# ART-Pi_F103_AP6212.net
KiCad netlist of a schematic drawn in Altium Designer
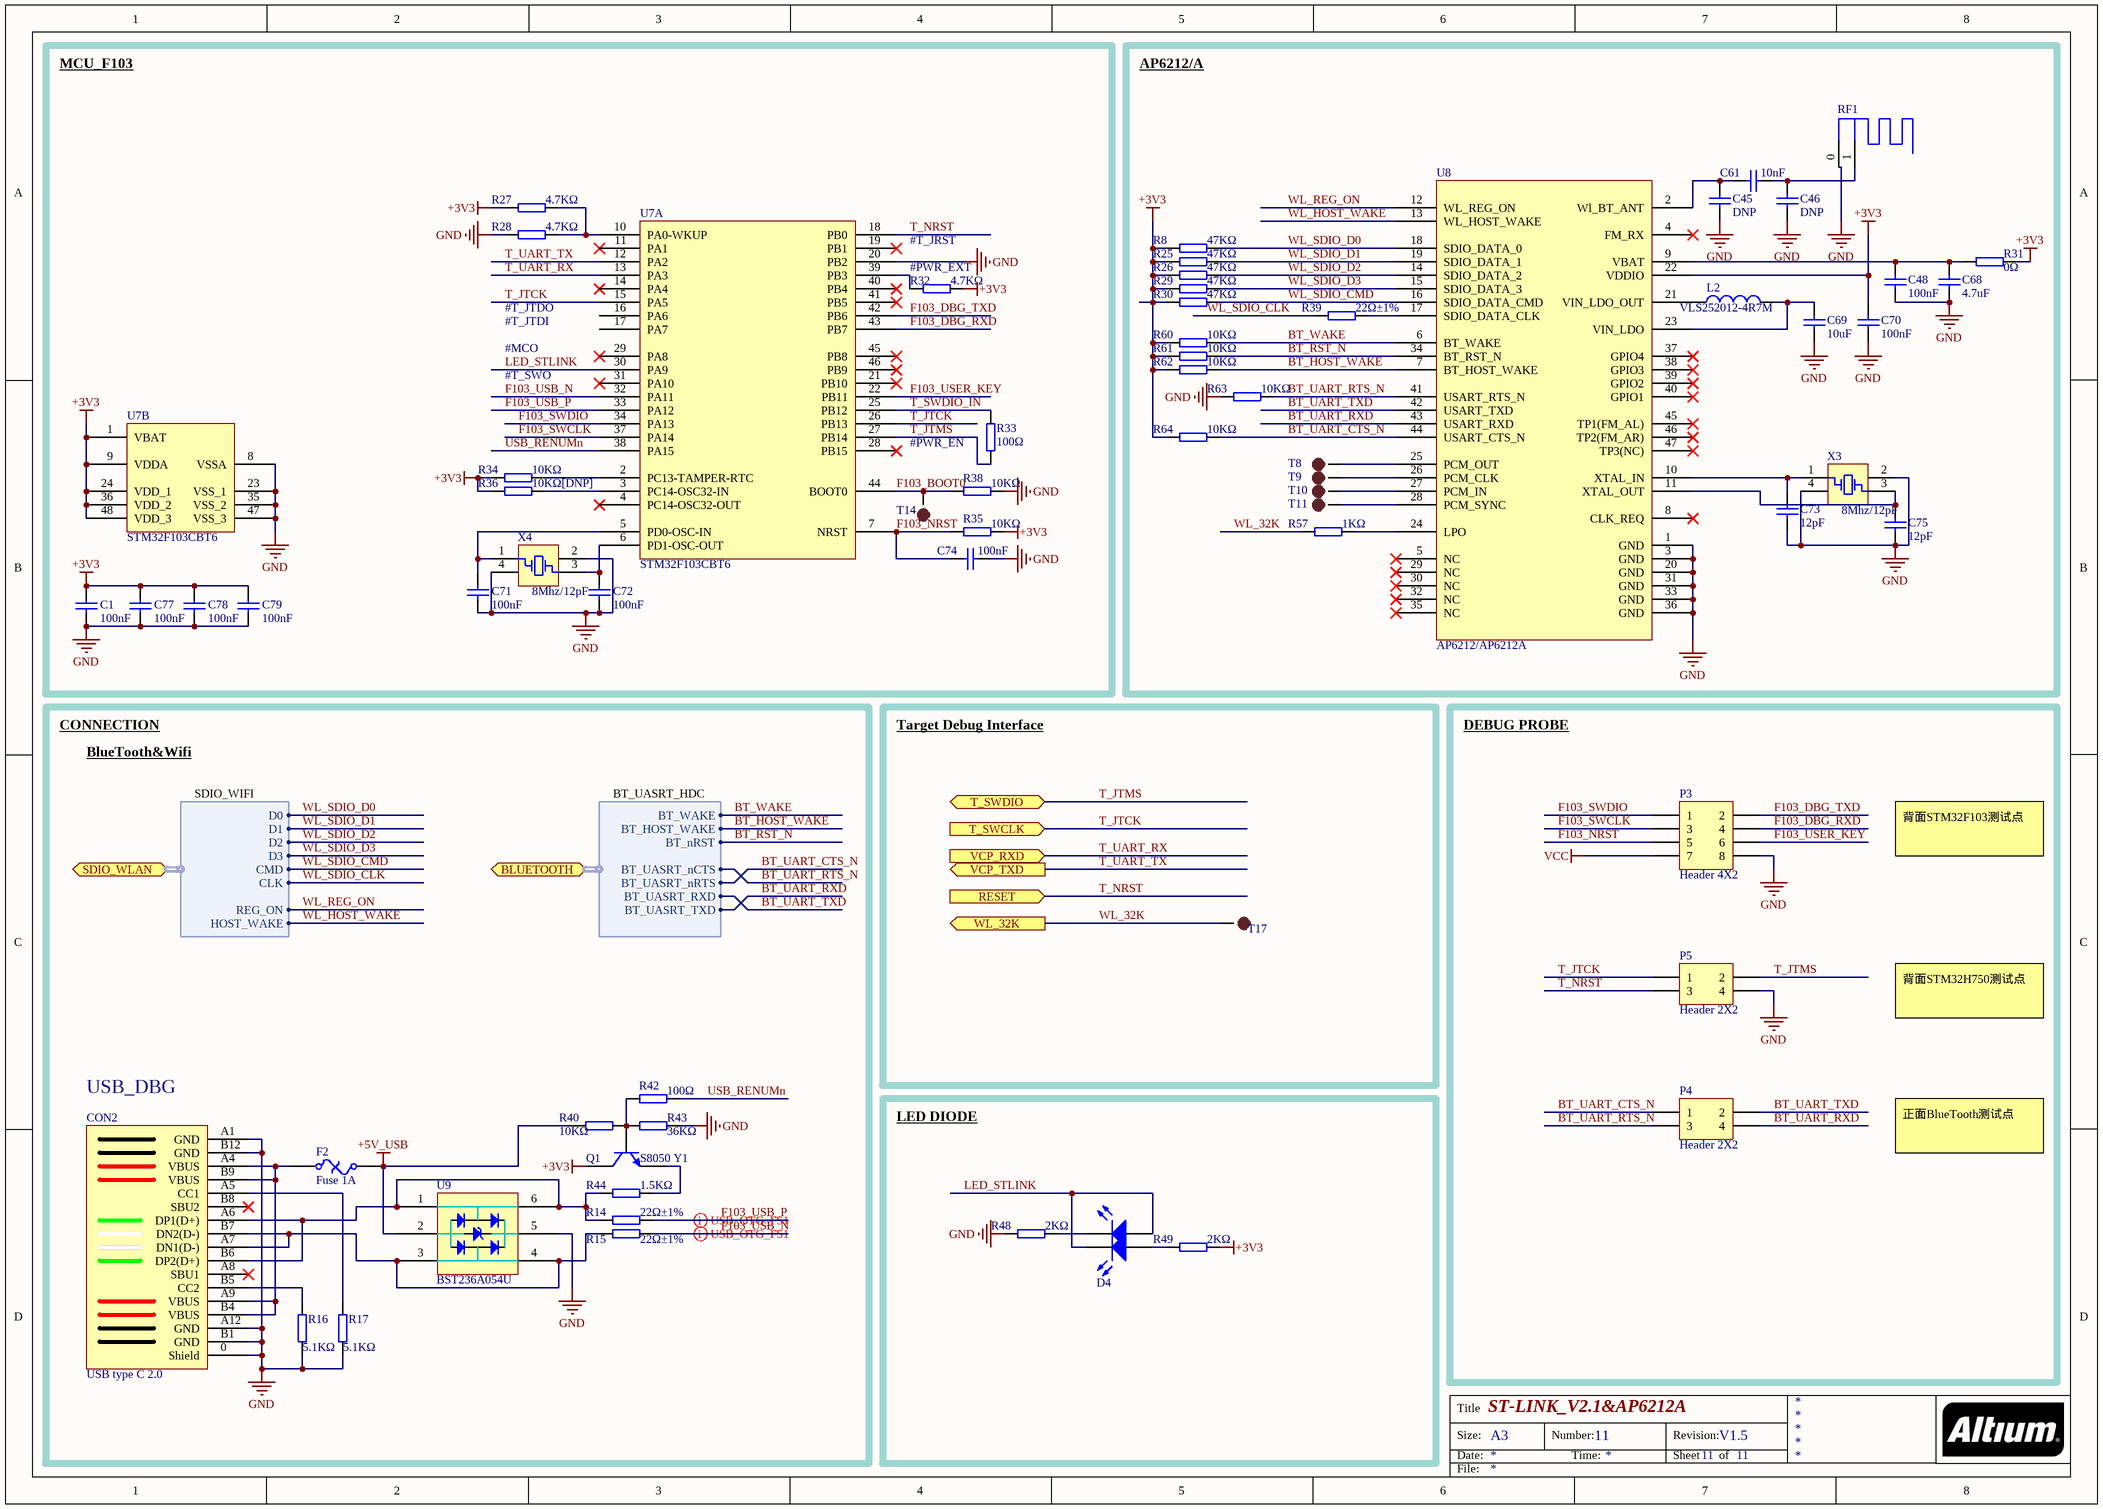
[diagram p0: ART-Pi_F103_AP6212.SchDoc]

(export (version "E")
  (design (tool "Eeschema 10.0.6"))
  (components
    (comp (ref "C1")
      (value "100nF")
      (footprint "0402_C")
      (description "Capacitor")
      (fields (field (name "PUBLISHER") "Altium Limited"))
      (libsource (lib "ART-Pi_STM32H750_COPY") (part "Cap"))
    )
    (comp (ref "C45")
      (value "DNP")
      (footprint "0402_C")
      (description "Capacitor")
      (fields (field (name "PUBLISHER") "Altium Limited"))
      (libsource (lib "ART-Pi_STM32H750_COPY") (part "Cap"))
    )
    (comp (ref "C46")
      (value "DNP")
      (footprint "0402_C")
      (description "Capacitor")
      (fields (field (name "PUBLISHER") "Altium Limited"))
      (libsource (lib "ART-Pi_STM32H750_COPY") (part "Cap"))
    )
    (comp (ref "C48")
      (value "100nF")
      (footprint "0402_C")
      (description "Capacitor")
      (fields (field (name "PUBLISHER") "Altium Limited"))
      (libsource (lib "ART-Pi_STM32H750_COPY") (part "Cap"))
    )
    (comp (ref "C61")
      (value "10nF")
      (footprint "0402_C")
      (description "Capacitor")
      (fields (field (name "PUBLISHER") "Altium Limited"))
      (libsource (lib "ART-Pi_STM32H750_COPY") (part "Cap"))
    )
    (comp (ref "C68")
      (value "4.7uF")
      (footprint "0402_C")
      (description "Capacitor")
      (fields (field (name "PUBLISHER") "Altium Limited"))
      (libsource (lib "ART-Pi_STM32H750_COPY") (part "Cap"))
    )
    (comp (ref "C69")
      (value "10uF")
      (footprint "0402_C")
      (description "Capacitor")
      (fields (field (name "PUBLISHER") "Altium Limited"))
      (libsource (lib "ART-Pi_STM32H750_COPY") (part "Cap"))
    )
    (comp (ref "C70")
      (value "100nF")
      (footprint "0402_C")
      (description "Capacitor")
      (fields (field (name "PUBLISHER") "Altium Limited"))
      (libsource (lib "ART-Pi_STM32H750_COPY") (part "Cap"))
    )
    (comp (ref "C71")
      (value "100nF")
      (footprint "0402_C")
      (description "Capacitor")
      (fields (field (name "PUBLISHER") "Altium Limited"))
      (libsource (lib "ART-Pi_STM32H750_COPY") (part "Cap"))
    )
    (comp (ref "C72")
      (value "100nF")
      (footprint "0402_C")
      (description "Capacitor")
      (fields (field (name "PUBLISHER") "Altium Limited"))
      (libsource (lib "ART-Pi_STM32H750_COPY") (part "Cap"))
    )
    (comp (ref "C73")
      (value "12pF")
      (footprint "0402_C")
      (description "Capacitor")
      (fields (field (name "PUBLISHER") "Altium Limited"))
      (libsource (lib "ART-Pi_STM32H750_COPY") (part "Cap"))
    )
    (comp (ref "C74")
      (value "100nF")
      (footprint "0402_C")
      (description "Capacitor")
      (fields (field (name "PUBLISHER") "Altium Limited"))
      (libsource (lib "ART-Pi_STM32H750_COPY") (part "Cap"))
    )
    (comp (ref "C75")
      (value "12pF")
      (footprint "0402_C")
      (description "Capacitor")
      (fields (field (name "PUBLISHER") "Altium Limited"))
      (libsource (lib "ART-Pi_STM32H750_COPY") (part "Cap"))
    )
    (comp (ref "C77")
      (value "100nF")
      (footprint "0402_C")
      (description "Capacitor")
      (fields (field (name "PUBLISHER") "Altium Limited"))
      (libsource (lib "ART-Pi_STM32H750_COPY") (part "Cap"))
    )
    (comp (ref "C78")
      (value "100nF")
      (footprint "0402_C")
      (description "Capacitor")
      (fields (field (name "PUBLISHER") "Altium Limited"))
      (libsource (lib "ART-Pi_STM32H750_COPY") (part "Cap"))
    )
    (comp (ref "C79")
      (value "100nF")
      (footprint "0402_C")
      (description "Capacitor")
      (fields (field (name "PUBLISHER") "Altium Limited"))
      (libsource (lib "ART-Pi_STM32H750_COPY") (part "Cap"))
    )
    (comp (ref "CON2")
      (value "USB type C 2.0")
      (footprint "USB_C")
      (libsource (lib "ART-Pi_STM32H750_COPY") (part "USB type C"))
    )
    (comp (ref "D4")
      (value "LED2")
      (footprint "LED2-0603")
      (description "Typical RED, GREEN, YELLOW, AMBER GaAs LED")
      (fields (field (name "PUBLISHER") "Altium Limited"))
      (libsource (lib "ART-Pi_STM32H750_COPY") (part "LED2"))
    )
    (comp (ref "F2")
      (value "Fuse 1A")
      (footprint "0805_R")
      (description "Thermal Fuse")
      (fields (field (name "PUBLISHER") "Altium Limited"))
      (libsource (lib "Miscellaneous Devices") (part "Fuse Thermal"))
    )
    (comp (ref "L2")
      (value "VLS252012-4R7M")
      (footprint "FNR252012S")
      (description "Inductor")
      (fields (field (name "PUBLISHER") "Altium Limited"))
      (libsource (lib "ART-Pi_STM32H750_COPY") (part "Inductor"))
    )
    (comp (ref "P3")
      (value "Header 4X2")
      (footprint "Test_Point_8")
      (description "Header, 4-Pin, Dual row")
      (fields (field (name "PUBLISHER") "Altium Limited"))
      (libsource (lib "Miscellaneous Connectors") (part "Header 4X2"))
    )
    (comp (ref "P4")
      (value "Header 2X2")
      (footprint "Test_Point_4")
      (description "Header, 2-Pin, Dual row")
      (fields (field (name "PUBLISHER") "Altium Limited"))
      (libsource (lib "Miscellaneous Connectors") (part "Header 2X2"))
    )
    (comp (ref "P5")
      (value "Header 2X2")
      (footprint "Test_Point_4")
      (description "Header, 2-Pin, Dual row")
      (fields (field (name "PUBLISHER") "Altium Limited"))
      (libsource (lib "Miscellaneous Connectors") (part "Header 2X2"))
    )
    (comp (ref "Q1")
      (value "S8050 Y1")
      (footprint "SOT23_P")
      (description "NPN Bipolar Transistor")
      (fields (field (name "PUBLISHER") "Altium Limited"))
      (libsource (lib "Miscellaneous Devices") (part "NPN"))
    )
    (comp (ref "R8")
      (value "47KΩ")
      (footprint "0402_R")
      (description "Resister")
      (libsource (lib "ART-Pi_STM32H750_COPY") (part "Res"))
    )
    (comp (ref "R14")
      (value "22Ω±1%")
      (footprint "0402_R")
      (description "Resister")
      (libsource (lib "ART-Pi_STM32H750_COPY") (part "Res"))
    )
    (comp (ref "R15")
      (value "22Ω±1%")
      (footprint "0402_R")
      (description "Resister")
      (libsource (lib "ART-Pi_STM32H750_COPY") (part "Res"))
    )
    (comp (ref "R16")
      (value "5.1KΩ")
      (footprint "0402_R")
      (description "Resister")
      (libsource (lib "ART-Pi_STM32H750_COPY") (part "Res"))
    )
    (comp (ref "R17")
      (value "5.1KΩ")
      (footprint "0402_R")
      (description "Resister")
      (libsource (lib "ART-Pi_STM32H750_COPY") (part "Res"))
    )
    (comp (ref "R25")
      (value "47KΩ")
      (footprint "0402_R")
      (description "Resister")
      (libsource (lib "ART-Pi_STM32H750_COPY") (part "Res"))
    )
    (comp (ref "R26")
      (value "47KΩ")
      (footprint "0402_R")
      (description "Resister")
      (libsource (lib "ART-Pi_STM32H750_COPY") (part "Res"))
    )
    (comp (ref "R27")
      (value "4.7KΩ")
      (footprint "0402_R")
      (description "Resister")
      (libsource (lib "ART-Pi_STM32H750_COPY") (part "Res"))
    )
    (comp (ref "R28")
      (value "4.7KΩ")
      (footprint "0402_R")
      (description "Resister")
      (libsource (lib "ART-Pi_STM32H750_COPY") (part "Res"))
    )
    (comp (ref "R29")
      (value "47KΩ")
      (footprint "0402_R")
      (description "Resister")
      (libsource (lib "ART-Pi_STM32H750_COPY") (part "Res"))
    )
    (comp (ref "R30")
      (value "47KΩ")
      (footprint "0402_R")
      (description "Resister")
      (libsource (lib "ART-Pi_STM32H750_COPY") (part "Res"))
    )
    (comp (ref "R31")
      (value "0Ω")
      (footprint "0402_R")
      (description "Resister")
      (libsource (lib "ART-Pi_STM32H750_COPY") (part "Res"))
    )
    (comp (ref "R32")
      (value "4.7KΩ")
      (footprint "0402_R")
      (description "Resister")
      (libsource (lib "ART-Pi_STM32H750_COPY") (part "Res"))
    )
    (comp (ref "R33")
      (value "100Ω")
      (footprint "0402_R")
      (description "Resister")
      (libsource (lib "ART-Pi_STM32H750_COPY") (part "Res"))
    )
    (comp (ref "R34")
      (value "10KΩ")
      (footprint "0402_R")
      (description "Resister")
      (libsource (lib "ART-Pi_STM32H750_COPY") (part "Res"))
    )
    (comp (ref "R35")
      (value "10KΩ")
      (footprint "0402_R")
      (description "Resister")
      (libsource (lib "ART-Pi_STM32H750_COPY") (part "Res"))
    )
    (comp (ref "R36")
      (value "10KΩ[DNP]")
      (footprint "0402_R")
      (description "Resister")
      (libsource (lib "ART-Pi_STM32H750_COPY") (part "Res"))
    )
    (comp (ref "R38")
      (value "10KΩ")
      (footprint "0402_R")
      (description "Resister")
      (libsource (lib "ART-Pi_STM32H750_COPY") (part "Res"))
    )
    (comp (ref "R39")
      (value "22Ω±1%")
      (footprint "0402_R")
      (description "Resister")
      (libsource (lib "ART-Pi_STM32H750_COPY") (part "Res"))
    )
    (comp (ref "R40")
      (value "10KΩ")
      (footprint "0402_R")
      (description "Resister")
      (libsource (lib "ART-Pi_STM32H750_COPY") (part "Res"))
    )
    (comp (ref "R42")
      (value "100Ω")
      (footprint "0402_R")
      (description "Resister")
      (libsource (lib "ART-Pi_STM32H750_COPY") (part "Res"))
    )
    (comp (ref "R43")
      (value "36KΩ")
      (footprint "0402_R")
      (description "Resister")
      (libsource (lib "ART-Pi_STM32H750_COPY") (part "Res"))
    )
    (comp (ref "R44")
      (value "1.5KΩ")
      (footprint "0402_R")
      (description "Resister")
      (libsource (lib "ART-Pi_STM32H750_COPY") (part "Res"))
    )
    (comp (ref "R48")
      (value "2KΩ")
      (footprint "0402_R")
      (description "Resister")
      (libsource (lib "ART-Pi_STM32H750_COPY") (part "Res"))
    )
    (comp (ref "R49")
      (value "2KΩ")
      (footprint "0402_R")
      (description "Resister")
      (libsource (lib "ART-Pi_STM32H750_COPY") (part "Res"))
    )
    (comp (ref "R57")
      (value "1KΩ")
      (footprint "0402_R")
      (description "Resister")
      (libsource (lib "ART-Pi_STM32H750_COPY") (part "Res"))
    )
    (comp (ref "R60")
      (value "10KΩ")
      (footprint "0402_R")
      (description "Resister")
      (libsource (lib "ART-Pi_STM32H750_COPY") (part "Res"))
    )
    (comp (ref "R61")
      (value "10KΩ")
      (footprint "0402_R")
      (description "Resister")
      (libsource (lib "ART-Pi_STM32H750_COPY") (part "Res"))
    )
    (comp (ref "R62")
      (value "10KΩ")
      (footprint "0402_R")
      (description "Resister")
      (libsource (lib "ART-Pi_STM32H750_COPY") (part "Res"))
    )
    (comp (ref "R63")
      (value "10KΩ")
      (footprint "0402_R")
      (description "Resister")
      (libsource (lib "ART-Pi_STM32H750_COPY") (part "Res"))
    )
    (comp (ref "R64")
      (value "10KΩ")
      (footprint "0402_R")
      (description "Resister")
      (libsource (lib "ART-Pi_STM32H750_COPY") (part "Res"))
    )
    (comp (ref "RF1")
      (value "ANT")
      (footprint "RF")
      (libsource (lib "ART-Pi_STM32H750_COPY") (part "PCB-ANT-2.4G-S"))
    )
    (comp (ref "T8")
      (value "TEST POINT")
      (footprint "Test_Point")
      (description "测试点")
      (libsource (lib "ART-Pi_STM32H750_COPY") (part "TEST-POINT"))
    )
    (comp (ref "T9")
      (value "TEST POINT")
      (footprint "Test_Point")
      (description "测试点")
      (libsource (lib "ART-Pi_STM32H750_COPY") (part "TEST-POINT"))
    )
    (comp (ref "T10")
      (value "TEST POINT")
      (footprint "Test_Point")
      (description "测试点")
      (libsource (lib "ART-Pi_STM32H750_COPY") (part "TEST-POINT"))
    )
    (comp (ref "T11")
      (value "TEST POINT")
      (footprint "Test_Point")
      (description "测试点")
      (libsource (lib "ART-Pi_STM32H750_COPY") (part "TEST-POINT"))
    )
    (comp (ref "T14")
      (value "TEST POINT")
      (footprint "Test_Point")
      (description "测试点")
      (libsource (lib "ART-Pi_STM32H750_COPY") (part "TEST-POINT"))
    )
    (comp (ref "T17")
      (value "TEST POINT")
      (footprint "Test_Point")
      (description "测试点")
      (libsource (lib "ART-Pi_STM32H750_COPY") (part "TEST-POINT"))
    )
    (comp (ref "U7")
      (value "STM32F103CBT6")
      (footprint "LQFP48_N")
      (libsource (lib "ART-Pi_STM32H750_COPY") (part "STM32F103CBT6"))
    )
    (comp (ref "U8")
      (value "AP6212/AP6212A")
      (footprint "AP6212A")
      (libsource (lib "ART-Pi_STM32H750_COPY") (part "AP6212/AP6212A"))
    )
    (comp (ref "U9")
      (value "BST236A054U")
      (footprint "SOT23_6")
      (libsource (lib "ART-Pi_STM32H750_COPY") (part "BST236A054U"))
    )
    (comp (ref "X3")
      (value "8Mhz/12pF")
      (footprint "SMD2520")
      (description "Crystal Oscillator")
      (fields (field (name "PUBLISHER") "Altium Limited"))
      (libsource (lib "ART-Pi_STM32H750_COPY") (part "XTAL_3225"))
    )
    (comp (ref "X4")
      (value "8Mhz/12pF")
      (footprint "XT-3225-4P")
      (description "Crystal Oscillator")
      (fields (field (name "PUBLISHER") "Altium Limited"))
      (libsource (lib "ART-Pi_STM32H750_COPY") (part "XTAL_3225"))
    )
  )
  (nets
    (net (code "2") (name "+3V3") (class "Default")
      (node (ref "C1") (pin "2") (pinfunction "2_2") (pintype "passive"))
      (node (ref "C70") (pin "1") (pinfunction "1_1") (pintype "passive"))
      (node (ref "C77") (pin "2") (pinfunction "2_2") (pintype "passive"))
      (node (ref "C78") (pin "2") (pinfunction "2_2") (pintype "passive"))
      (node (ref "C79") (pin "2") (pinfunction "2_2") (pintype "passive"))
      (node (ref "Q1") (pin "1") (pinfunction "C_1") (pintype "passive"))
      (node (ref "R25") (pin "1") (pinfunction "1_1") (pintype "passive"))
      (node (ref "R26") (pin "1") (pinfunction "1_1") (pintype "passive"))
      (node (ref "R27") (pin "2") (pinfunction "2_2") (pintype "passive"))
      (node (ref "R29") (pin "1") (pinfunction "1_1") (pintype "passive"))
      (node (ref "R30") (pin "1") (pinfunction "1_1") (pintype "passive"))
      (node (ref "R31") (pin "2") (pinfunction "2_2") (pintype "passive"))
      (node (ref "R32") (pin "1") (pinfunction "1_1") (pintype "passive"))
      (node (ref "R34") (pin "2") (pinfunction "2_2") (pintype "passive"))
      (node (ref "R35") (pin "2") (pinfunction "2_2") (pintype "passive"))
      (node (ref "R36") (pin "2") (pinfunction "2_2") (pintype "passive"))
      (node (ref "R49") (pin "2") (pinfunction "2_2") (pintype "passive"))
      (node (ref "R60") (pin "1") (pinfunction "1_1") (pintype "passive"))
      (node (ref "R61") (pin "1") (pinfunction "1_1") (pintype "passive"))
      (node (ref "R62") (pin "1") (pinfunction "1_1") (pintype "passive"))
      (node (ref "R64") (pin "1") (pinfunction "1_1") (pintype "passive"))
      (node (ref "R8") (pin "1") (pinfunction "1_1") (pintype "passive"))
      (node (ref "U7") (pin "1") (pinfunction "VBAT_1") (pintype "passive"))
      (node (ref "U7") (pin "24") (pinfunction "VDD_1_24") (pintype "passive"))
      (node (ref "U7") (pin "36") (pinfunction "VDD_2_36") (pintype "passive"))
      (node (ref "U7") (pin "48") (pinfunction "VDD_3_48") (pintype "passive"))
      (node (ref "U7") (pin "9") (pinfunction "VDDA_9") (pintype "passive"))
      (node (ref "U8") (pin "22") (pinfunction "VDDIO_22") (pintype "passive"))
    )
    (net (code "3") (name "+5V_USB") (class "Default")
      (node (ref "F2") (pin "2") (pinfunction "2_2") (pintype "passive"))
      (node (ref "R40") (pin "1") (pinfunction "1_1") (pintype "passive"))
      (node (ref "U9") (pin "2") (pinfunction "2_2") (pintype "passive"))
    )
    (net (code "4") (name "/BT_HOST_WAKE") (class "Default")
      (node (ref "R62") (pin "2") (pinfunction "2_2") (pintype "passive"))
      (node (ref "U8") (pin "7") (pinfunction "BT_HOST_WAKE_7") (pintype "passive"))
    )
    (net (code "5") (name "/BT_RST_N") (class "Default")
      (node (ref "R61") (pin "2") (pinfunction "2_2") (pintype "passive"))
      (node (ref "U8") (pin "34") (pinfunction "BT_RST_N_34") (pintype "passive"))
    )
    (net (code "6") (name "/BT_UART_CTS_N") (class "Default")
      (node (ref "P4") (pin "1") (pinfunction "1_1") (pintype "passive"))
      (node (ref "R64") (pin "2") (pinfunction "2_2") (pintype "passive"))
      (node (ref "U8") (pin "44") (pinfunction "USART_CTS_N_44") (pintype "passive"))
    )
    (net (code "7") (name "/BT_UART_RTS_N") (class "Default")
      (node (ref "P4") (pin "3") (pinfunction "3_3") (pintype "passive"))
      (node (ref "R63") (pin "2") (pinfunction "2_2") (pintype "passive"))
      (node (ref "U8") (pin "41") (pinfunction "USART_RTS_N_41") (pintype "passive"))
    )
    (net (code "8") (name "/BT_UART_RXD") (class "Default")
      (node (ref "P4") (pin "4") (pinfunction "4_4") (pintype "passive"))
      (node (ref "U8") (pin "43") (pinfunction "USART_RXD_43") (pintype "passive"))
    )
    (net (code "9") (name "/BT_UART_TXD") (class "Default")
      (node (ref "P4") (pin "2") (pinfunction "2_2") (pintype "passive"))
      (node (ref "U8") (pin "42") (pinfunction "USART_TXD_42") (pintype "passive"))
    )
    (net (code "10") (name "/BT_WAKE") (class "Default")
      (node (ref "R60") (pin "2") (pinfunction "2_2") (pintype "passive"))
      (node (ref "U8") (pin "6") (pinfunction "BT_WAKE_6") (pintype "passive"))
    )
    (net (code "11") (name "/F103_BOOT0") (class "Default")
      (node (ref "R38") (pin "1") (pinfunction "1_1") (pintype "passive"))
      (node (ref "T14") (pin "1") (pinfunction "1_1") (pintype "passive"))
      (node (ref "U7") (pin "44") (pinfunction "BOOT0_44") (pintype "passive"))
    )
    (net (code "12") (name "/F103_DBG_RXD") (class "Default")
      (node (ref "P3") (pin "4") (pinfunction "4_4") (pintype "passive"))
      (node (ref "U7") (pin "43") (pinfunction "PB7_43") (pintype "passive"))
    )
    (net (code "13") (name "/F103_DBG_TXD") (class "Default")
      (node (ref "P3") (pin "2") (pinfunction "2_2") (pintype "passive"))
      (node (ref "U7") (pin "42") (pinfunction "PB6_42") (pintype "passive"))
    )
    (net (code "14") (name "/F103_NRST") (class "Default")
      (node (ref "C74") (pin "2") (pinfunction "2_2") (pintype "passive"))
      (node (ref "P3") (pin "5") (pinfunction "5_5") (pintype "passive"))
      (node (ref "R35") (pin "1") (pinfunction "1_1") (pintype "passive"))
      (node (ref "U7") (pin "7") (pinfunction "NRST_7") (pintype "passive"))
    )
    (net (code "15") (name "/F103_SWCLK") (class "Default")
      (node (ref "P3") (pin "3") (pinfunction "3_3") (pintype "passive"))
      (node (ref "U7") (pin "37") (pinfunction "PA14_37") (pintype "passive"))
    )
    (net (code "16") (name "/F103_SWDIO") (class "Default")
      (node (ref "P3") (pin "1") (pinfunction "1_1") (pintype "passive"))
      (node (ref "U7") (pin "34") (pinfunction "PA13_34") (pintype "passive"))
    )
    (net (code "17") (name "/F103_USB_N") (class "Default")
      (node (ref "R15") (pin "2") (pinfunction "2_2") (pintype "passive"))
      (node (ref "U7") (pin "32") (pinfunction "PA11_32") (pintype "passive"))
    )
    (net (code "18") (name "/F103_USB_P") (class "Default")
      (node (ref "R14") (pin "2") (pinfunction "2_2") (pintype "passive"))
      (node (ref "U7") (pin "33") (pinfunction "PA12_33") (pintype "passive"))
    )
    (net (code "19") (name "/F103_USER_KEY") (class "Default")
      (node (ref "P3") (pin "6") (pinfunction "6_6") (pintype "passive"))
      (node (ref "U7") (pin "22") (pinfunction "PB11_22") (pintype "passive"))
    )
    (net (code "20") (name "/LED_STLINK") (class "Default")
      (node (ref "D4") (pin "2") (pinfunction "2_2") (pintype "passive"))
      (node (ref "D4") (pin "4") (pinfunction "4_4") (pintype "passive"))
      (node (ref "U7") (pin "30") (pinfunction "PA9_30") (pintype "passive"))
    )
    (net (code "21") (name "/T_JTCK") (class "Default")
      (node (ref "P5") (pin "1") (pinfunction "1_1") (pintype "passive"))
      (node (ref "U7") (pin "15") (pinfunction "PA5_15") (pintype "passive"))
      (node (ref "U7") (pin "26") (pinfunction "PB13_26") (pintype "passive"))
    )
    (net (code "22") (name "/T_JTMS") (class "Default")
      (node (ref "P5") (pin "2") (pinfunction "2_2") (pintype "passive"))
      (node (ref "R33") (pin "2") (pinfunction "2_2") (pintype "passive"))
      (node (ref "U7") (pin "27") (pinfunction "PB14_27") (pintype "passive"))
    )
    (net (code "23") (name "/T_NRST") (class "Default")
      (node (ref "P5") (pin "3") (pinfunction "3_3") (pintype "passive"))
      (node (ref "U7") (pin "18") (pinfunction "PB0_18") (pintype "passive"))
    )
    (net (code "24") (name "/T_SWDIO_IN") (class "Default")
      (node (ref "R33") (pin "1") (pinfunction "1_1") (pintype "passive"))
      (node (ref "U7") (pin "25") (pinfunction "PB12_25") (pintype "passive"))
    )
    (net (code "25") (name "/T_UART_RX") (class "Default")
      (node (ref "U7") (pin "13") (pinfunction "PA3_13") (pintype "passive"))
    )
    (net (code "26") (name "/T_UART_TX") (class "Default")
      (node (ref "U7") (pin "12") (pinfunction "PA2_12") (pintype "passive"))
    )
    (net (code "27") (name "/USB_RENUMn") (class "Default")
      (node (ref "R42") (pin "2") (pinfunction "2_2") (pintype "passive"))
      (node (ref "U7") (pin "38") (pinfunction "PA15_38") (pintype "passive"))
    )
    (net (code "28") (name "/WL_32K") (class "Default")
      (node (ref "R57") (pin "1") (pinfunction "1_1") (pintype "passive"))
      (node (ref "T17") (pin "1") (pinfunction "1_1") (pintype "passive"))
    )
    (net (code "29") (name "/WL_HOST_WAKE") (class "Default")
      (node (ref "U8") (pin "13") (pinfunction "WL_HOST_WAKE_13") (pintype "passive"))
    )
    (net (code "30") (name "/WL_REG_ON") (class "Default")
      (node (ref "U8") (pin "12") (pinfunction "WL_REG_ON_12") (pintype "passive"))
    )
    (net (code "31") (name "/WL_SDIO_CLK") (class "Default")
      (node (ref "R39") (pin "1") (pinfunction "1_1") (pintype "passive"))
    )
    (net (code "32") (name "/WL_SDIO_CMD") (class "Default")
      (node (ref "R30") (pin "2") (pinfunction "2_2") (pintype "passive"))
      (node (ref "U8") (pin "16") (pinfunction "SDIO_DATA_CMD_16") (pintype "passive"))
    )
    (net (code "33") (name "/WL_SDIO_D0") (class "Default")
      (node (ref "R8") (pin "2") (pinfunction "2_2") (pintype "passive"))
      (node (ref "U8") (pin "18") (pinfunction "SDIO_DATA_0_18") (pintype "passive"))
    )
    (net (code "34") (name "/WL_SDIO_D1") (class "Default")
      (node (ref "R25") (pin "2") (pinfunction "2_2") (pintype "passive"))
      (node (ref "U8") (pin "19") (pinfunction "SDIO_DATA_1_19") (pintype "passive"))
    )
    (net (code "35") (name "/WL_SDIO_D2") (class "Default")
      (node (ref "R26") (pin "2") (pinfunction "2_2") (pintype "passive"))
      (node (ref "U8") (pin "14") (pinfunction "SDIO_DATA_2_14") (pintype "passive"))
    )
    (net (code "36") (name "/WL_SDIO_D3") (class "Default")
      (node (ref "R29") (pin "2") (pinfunction "2_2") (pintype "passive"))
      (node (ref "U8") (pin "15") (pinfunction "SDIO_DATA_3_15") (pintype "passive"))
    )
    (net (code "38") (name "GND") (class "Default")
      (node (ref "C1") (pin "1") (pinfunction "1_1") (pintype "passive"))
      (node (ref "C45") (pin "2") (pinfunction "2_2") (pintype "passive"))
      (node (ref "C46") (pin "2") (pinfunction "2_2") (pintype "passive"))
      (node (ref "C48") (pin "2") (pinfunction "2_2") (pintype "passive"))
      (node (ref "C68") (pin "2") (pinfunction "2_2") (pintype "passive"))
      (node (ref "C69") (pin "2") (pinfunction "2_2") (pintype "passive"))
      (node (ref "C70") (pin "2") (pinfunction "2_2") (pintype "passive"))
      (node (ref "C71") (pin "1") (pinfunction "1_1") (pintype "passive"))
      (node (ref "C72") (pin "1") (pinfunction "1_1") (pintype "passive"))
      (node (ref "C73") (pin "2") (pinfunction "2_2") (pintype "passive"))
      (node (ref "C74") (pin "1") (pinfunction "1_1") (pintype "passive"))
      (node (ref "C75") (pin "2") (pinfunction "2_2") (pintype "passive"))
      (node (ref "C77") (pin "1") (pinfunction "1_1") (pintype "passive"))
      (node (ref "C78") (pin "1") (pinfunction "1_1") (pintype "passive"))
      (node (ref "C79") (pin "1") (pinfunction "1_1") (pintype "passive"))
      (node (ref "CON2") (pin "0") (pinfunction "Shield_0") (pintype "passive"))
      (node (ref "CON2") (pin "A1") (pinfunction "GND_A1") (pintype "passive"))
      (node (ref "CON2") (pin "A12") (pinfunction "GND_A12") (pintype "passive"))
      (node (ref "CON2") (pin "B1") (pinfunction "GND_B1") (pintype "passive"))
      (node (ref "CON2") (pin "B12") (pinfunction "GND_B12") (pintype "passive"))
      (node (ref "P3") (pin "8") (pinfunction "8_8") (pintype "passive"))
      (node (ref "P5") (pin "4") (pinfunction "4_4") (pintype "passive"))
      (node (ref "R16") (pin "2") (pinfunction "2_2") (pintype "passive"))
      (node (ref "R17") (pin "2") (pinfunction "2_2") (pintype "passive"))
      (node (ref "R28") (pin "2") (pinfunction "2_2") (pintype "passive"))
      (node (ref "R38") (pin "2") (pinfunction "2_2") (pintype "passive"))
      (node (ref "R43") (pin "2") (pinfunction "2_2") (pintype "passive"))
      (node (ref "R48") (pin "1") (pinfunction "1_1") (pintype "passive"))
      (node (ref "R63") (pin "1") (pinfunction "1_1") (pintype "passive"))
      (node (ref "RF1") (pin "0") (pinfunction "0_0") (pintype "passive"))
      (node (ref "U7") (pin "20") (pinfunction "PB2_20") (pintype "passive"))
      (node (ref "U7") (pin "23") (pinfunction "VSS_1_23") (pintype "passive"))
      (node (ref "U7") (pin "35") (pinfunction "VSS_2_35") (pintype "passive"))
      (node (ref "U7") (pin "47") (pinfunction "VSS_3_47") (pintype "passive"))
      (node (ref "U7") (pin "8") (pinfunction "VSSA_8") (pintype "passive"))
      (node (ref "U8") (pin "1") (pinfunction "GND_1") (pintype "passive"))
      (node (ref "U8") (pin "20") (pinfunction "GND_20") (pintype "passive"))
      (node (ref "U8") (pin "3") (pinfunction "GND_3") (pintype "passive"))
      (node (ref "U8") (pin "31") (pinfunction "GND_31") (pintype "passive"))
      (node (ref "U8") (pin "33") (pinfunction "GND_33") (pintype "passive"))
      (node (ref "U8") (pin "36") (pinfunction "GND_36") (pintype "passive"))
      (node (ref "U9") (pin "5") (pinfunction "5_5") (pintype "passive"))
      (node (ref "X3") (pin "2") (pinfunction "OSC2_2") (pintype "passive"))
      (node (ref "X3") (pin "4") (pinfunction "4_4") (pintype "passive"))
      (node (ref "X4") (pin "2") (pinfunction "OSC2_2") (pintype "passive"))
      (node (ref "X4") (pin "4") (pinfunction "4_4") (pintype "passive"))
    )
    (net (code "39") (name "Net-(C46-Pad1)") (class "Default")
      (node (ref "C46") (pin "1") (pinfunction "1_1") (pintype "passive"))
      (node (ref "C61") (pin "1") (pinfunction "1_1") (pintype "passive"))
      (node (ref "RF1") (pin "1") (pinfunction "1_1") (pintype "passive"))
    )
    (net (code "40") (name "Net-(CON2-CC1)") (class "Default")
      (node (ref "CON2") (pin "A5") (pinfunction "CC1_A5") (pintype "passive"))
      (node (ref "R17") (pin "1") (pinfunction "1_1") (pintype "passive"))
    )
    (net (code "41") (name "Net-(CON2-CC2)") (class "Default")
      (node (ref "CON2") (pin "B5") (pinfunction "CC2_B5") (pintype "passive"))
      (node (ref "R16") (pin "1") (pinfunction "1_1") (pintype "passive"))
    )
    (net (code "42") (name "Net-(CON2-DN1(D-))") (class "Default")
      (node (ref "CON2") (pin "A7") (pinfunction "DN1(D-)_A7") (pintype "passive"))
      (node (ref "CON2") (pin "B7") (pinfunction "DN2(D-)_B7") (pintype "passive"))
      (node (ref "R15") (pin "1") (pinfunction "1_1") (pintype "passive"))
      (node (ref "U9") (pin "3") (pinfunction "3_3") (pintype "passive"))
      (node (ref "U9") (pin "4") (pinfunction "4_4") (pintype "passive"))
    )
    (net (code "43") (name "Net-(CON2-DP1(D+))") (class "Default")
      (node (ref "CON2") (pin "A6") (pinfunction "DP1(D+)_A6") (pintype "passive"))
      (node (ref "CON2") (pin "B6") (pinfunction "DP2(D+)_B6") (pintype "passive"))
      (node (ref "R14") (pin "1") (pinfunction "1_1") (pintype "passive"))
      (node (ref "R44") (pin "1") (pinfunction "1_1") (pintype "passive"))
      (node (ref "U9") (pin "1") (pinfunction "1_1") (pintype "passive"))
      (node (ref "U9") (pin "6") (pinfunction "6_6") (pintype "passive"))
    )
    (net (code "44") (name "Net-(CON2-VBUS-PadA4)") (class "Default")
      (node (ref "CON2") (pin "A4") (pinfunction "VBUS_A4") (pintype "passive"))
      (node (ref "CON2") (pin "A9") (pinfunction "VBUS_A9") (pintype "passive"))
      (node (ref "CON2") (pin "B4") (pinfunction "VBUS_B4") (pintype "passive"))
      (node (ref "CON2") (pin "B9") (pinfunction "VBUS_B9") (pintype "passive"))
      (node (ref "F2") (pin "1") (pinfunction "1_1") (pintype "passive"))
    )
    (net (code "45") (name "Net-(D4-Pad1)") (class "Default")
      (node (ref "D4") (pin "1") (pinfunction "1_1") (pintype "passive"))
      (node (ref "R49") (pin "1") (pinfunction "1_1") (pintype "passive"))
    )
    (net (code "46") (name "Net-(D4-Pad3)") (class "Default")
      (node (ref "D4") (pin "3") (pinfunction "3_3") (pintype "passive"))
      (node (ref "R48") (pin "2") (pinfunction "2_2") (pintype "passive"))
    )
    (net (code "47") (name "Net-(Q1-B)") (class "Default")
      (node (ref "Q1") (pin "3") (pinfunction "B_3") (pintype "passive"))
      (node (ref "R40") (pin "2") (pinfunction "2_2") (pintype "passive"))
      (node (ref "R42") (pin "1") (pinfunction "1_1") (pintype "passive"))
      (node (ref "R43") (pin "1") (pinfunction "1_1") (pintype "passive"))
    )
    (net (code "48") (name "Net-(Q1-E)") (class "Default")
      (node (ref "Q1") (pin "2") (pinfunction "E_2") (pintype "passive"))
      (node (ref "R44") (pin "2") (pinfunction "2_2") (pintype "passive"))
    )
    (net (code "49") (name "Net-(U7A-PA0-WKUP)") (class "Default")
      (node (ref "R27") (pin "1") (pinfunction "1_1") (pintype "passive"))
      (node (ref "R28") (pin "1") (pinfunction "1_1") (pintype "passive"))
      (node (ref "U7") (pin "10") (pinfunction "PA0-WKUP_10") (pintype "passive"))
    )
    (net (code "50") (name "Net-(U7A-PB3)") (class "Default")
      (node (ref "R32") (pin "2") (pinfunction "2_2") (pintype "passive"))
      (node (ref "U7") (pin "39") (pinfunction "PB3_39") (pintype "passive"))
    )
    (net (code "51") (name "Net-(U7A-PC13-TAMPER-RTC)") (class "Default")
      (node (ref "R34") (pin "1") (pinfunction "1_1") (pintype "passive"))
      (node (ref "U7") (pin "2") (pinfunction "PC13-TAMPER-RTC_2") (pintype "passive"))
    )
    (net (code "52") (name "Net-(U7A-PC14-OSC32-IN)") (class "Default")
      (node (ref "R36") (pin "1") (pinfunction "1_1") (pintype "passive"))
      (node (ref "U7") (pin "3") (pinfunction "PC14-OSC32-IN_3") (pintype "passive"))
    )
    (net (code "53") (name "Net-(U7A-PD-OSC-IN)") (class "Default")
      (node (ref "C71") (pin "2") (pinfunction "2_2") (pintype "passive"))
      (node (ref "U7") (pin "5") (pinfunction "PD-OSC-IN_5") (pintype "passive"))
      (node (ref "X4") (pin "1") (pinfunction "OSC1_1") (pintype "passive"))
    )
    (net (code "54") (name "Net-(U7A-PD1-OSC-OUT)") (class "Default")
      (node (ref "C72") (pin "2") (pinfunction "2_2") (pintype "passive"))
      (node (ref "U7") (pin "6") (pinfunction "PD1-OSC-OUT_6") (pintype "passive"))
      (node (ref "X4") (pin "3") (pinfunction "3_3") (pintype "passive"))
    )
    (net (code "55") (name "Net-(U8-LPO)") (class "Default")
      (node (ref "R57") (pin "2") (pinfunction "2_2") (pintype "passive"))
      (node (ref "U8") (pin "24") (pinfunction "LPO_24") (pintype "passive"))
    )
    (net (code "56") (name "Net-(U8-PCM_CLK)") (class "Default")
      (node (ref "T9") (pin "1") (pinfunction "1_1") (pintype "passive"))
      (node (ref "U8") (pin "26") (pinfunction "PCM_CLK_26") (pintype "passive"))
    )
    (net (code "57") (name "Net-(U8-PCM_IN)") (class "Default")
      (node (ref "T10") (pin "1") (pinfunction "1_1") (pintype "passive"))
      (node (ref "U8") (pin "27") (pinfunction "PCM_IN_27") (pintype "passive"))
    )
    (net (code "58") (name "Net-(U8-PCM_OUT)") (class "Default")
      (node (ref "T8") (pin "1") (pinfunction "1_1") (pintype "passive"))
      (node (ref "U8") (pin "25") (pinfunction "PCM_OUT_25") (pintype "passive"))
    )
    (net (code "59") (name "Net-(U8-PCM_SYNC)") (class "Default")
      (node (ref "T11") (pin "1") (pinfunction "1_1") (pintype "passive"))
      (node (ref "U8") (pin "28") (pinfunction "PCM_SYNC_28") (pintype "passive"))
    )
    (net (code "60") (name "Net-(U8-SDIO_DATA_CLK)") (class "Default")
      (node (ref "R39") (pin "2") (pinfunction "2_2") (pintype "passive"))
      (node (ref "U8") (pin "17") (pinfunction "SDIO_DATA_CLK_17") (pintype "passive"))
    )
    (net (code "61") (name "Net-(U8-VBAT)") (class "Default")
      (node (ref "C48") (pin "1") (pinfunction "1_1") (pintype "passive"))
      (node (ref "C68") (pin "1") (pinfunction "1_1") (pintype "passive"))
      (node (ref "R31") (pin "1") (pinfunction "1_1") (pintype "passive"))
      (node (ref "U8") (pin "9") (pinfunction "VBAT_9") (pintype "passive"))
    )
    (net (code "62") (name "Net-(U8-VIN_LDO)") (class "Default")
      (node (ref "C69") (pin "1") (pinfunction "1_1") (pintype "passive"))
      (node (ref "L2") (pin "2") (pinfunction "2_2") (pintype "passive"))
      (node (ref "U8") (pin "23") (pinfunction "VIN_LDO_23") (pintype "passive"))
    )
    (net (code "63") (name "Net-(U8-VIN_LDO_OUT)") (class "Default")
      (node (ref "L2") (pin "1") (pinfunction "1_1") (pintype "passive"))
      (node (ref "U8") (pin "21") (pinfunction "VIN_LDO_OUT_21") (pintype "passive"))
    )
    (net (code "64") (name "Net-(U8-Wl_BT_ANT)") (class "Default")
      (node (ref "C45") (pin "1") (pinfunction "1_1") (pintype "passive"))
      (node (ref "C61") (pin "2") (pinfunction "2_2") (pintype "passive"))
      (node (ref "U8") (pin "2") (pinfunction "Wl_BT_ANT_2") (pintype "passive"))
    )
    (net (code "65") (name "Net-(U8-XTAL_IN)") (class "Default")
      (node (ref "C73") (pin "1") (pinfunction "1_1") (pintype "passive"))
      (node (ref "U8") (pin "10") (pinfunction "XTAL_IN_10") (pintype "passive"))
      (node (ref "X3") (pin "1") (pinfunction "OSC1_1") (pintype "passive"))
    )
    (net (code "66") (name "Net-(U8-XTAL_OUT)") (class "Default")
      (node (ref "C75") (pin "1") (pinfunction "1_1") (pintype "passive"))
      (node (ref "U8") (pin "11") (pinfunction "XTAL_OUT_11") (pintype "passive"))
      (node (ref "X3") (pin "3") (pinfunction "3_3") (pintype "passive"))
    )
    (net (code "67") (name "VCC") (class "Default")
      (node (ref "P3") (pin "7") (pinfunction "7_7") (pintype "passive"))
    )
    (net (code "68") (name "unconnected-(CON2-SBU1-PadA8)") (class "Default")
      (node (ref "CON2") (pin "A8") (pinfunction "SBU1_A8") (pintype "passive+no_connect"))
    )
    (net (code "69") (name "unconnected-(CON2-SBU2-PadB8)") (class "Default")
      (node (ref "CON2") (pin "B8") (pinfunction "SBU2_B8") (pintype "passive+no_connect"))
    )
    (net (code "70") (name "unconnected-(U7A-PA1-Pad11)") (class "Default")
      (node (ref "U7") (pin "11") (pinfunction "PA1_11") (pintype "passive+no_connect"))
    )
    (net (code "71") (name "unconnected-(U7A-PA4-Pad14)") (class "Default")
      (node (ref "U7") (pin "14") (pinfunction "PA4_14") (pintype "passive+no_connect"))
    )
    (net (code "72") (name "unconnected-(U7A-PA6-Pad16)") (class "Default")
      (node (ref "U7") (pin "16") (pinfunction "PA6_16") (pintype "passive"))
    )
    (net (code "73") (name "unconnected-(U7A-PA7-Pad17)") (class "Default")
      (node (ref "U7") (pin "17") (pinfunction "PA7_17") (pintype "passive"))
    )
    (net (code "74") (name "unconnected-(U7A-PA8-Pad29)") (class "Default")
      (node (ref "U7") (pin "29") (pinfunction "PA8_29") (pintype "passive+no_connect"))
    )
    (net (code "75") (name "unconnected-(U7A-PA10-Pad31)") (class "Default")
      (node (ref "U7") (pin "31") (pinfunction "PA10_31") (pintype "passive+no_connect"))
    )
    (net (code "76") (name "unconnected-(U7A-PB1-Pad19)") (class "Default")
      (node (ref "U7") (pin "19") (pinfunction "PB1_19") (pintype "passive+no_connect"))
    )
    (net (code "77") (name "unconnected-(U7A-PB4-Pad40)") (class "Default")
      (node (ref "U7") (pin "40") (pinfunction "PB4_40") (pintype "passive+no_connect"))
    )
    (net (code "78") (name "unconnected-(U7A-PB5-Pad41)") (class "Default")
      (node (ref "U7") (pin "41") (pinfunction "PB5_41") (pintype "passive+no_connect"))
    )
    (net (code "79") (name "unconnected-(U7A-PB8-Pad45)") (class "Default")
      (node (ref "U7") (pin "45") (pinfunction "PB8_45") (pintype "passive+no_connect"))
    )
    (net (code "80") (name "unconnected-(U7A-PB9-Pad46)") (class "Default")
      (node (ref "U7") (pin "46") (pinfunction "PB9_46") (pintype "passive+no_connect"))
    )
    (net (code "81") (name "unconnected-(U7A-PB10-Pad21)") (class "Default")
      (node (ref "U7") (pin "21") (pinfunction "PB10_21") (pintype "passive+no_connect"))
    )
    (net (code "82") (name "unconnected-(U7A-PB15-Pad28)") (class "Default")
      (node (ref "U7") (pin "28") (pinfunction "PB15_28") (pintype "passive+no_connect"))
    )
    (net (code "83") (name "unconnected-(U7A-PC14-OSC32-OUT-Pad4)") (class "Default")
      (node (ref "U7") (pin "4") (pinfunction "PC14-OSC32-OUT_4") (pintype "passive+no_connect"))
    )
    (net (code "84") (name "unconnected-(U8-CLK_REQ-Pad8)") (class "Default")
      (node (ref "U8") (pin "8") (pinfunction "CLK_REQ_8") (pintype "passive+no_connect"))
    )
    (net (code "85") (name "unconnected-(U8-FM_RX-Pad4)") (class "Default")
      (node (ref "U8") (pin "4") (pinfunction "FM_RX_4") (pintype "passive+no_connect"))
    )
    (net (code "86") (name "unconnected-(U8-GPIO1-Pad40)") (class "Default")
      (node (ref "U8") (pin "40") (pinfunction "GPIO1_40") (pintype "passive+no_connect"))
    )
    (net (code "87") (name "unconnected-(U8-GPIO2-Pad39)") (class "Default")
      (node (ref "U8") (pin "39") (pinfunction "GPIO2_39") (pintype "passive+no_connect"))
    )
    (net (code "88") (name "unconnected-(U8-GPIO3-Pad38)") (class "Default")
      (node (ref "U8") (pin "38") (pinfunction "GPIO3_38") (pintype "passive+no_connect"))
    )
    (net (code "89") (name "unconnected-(U8-GPIO4-Pad37)") (class "Default")
      (node (ref "U8") (pin "37") (pinfunction "GPIO4_37") (pintype "passive+no_connect"))
    )
    (net (code "90") (name "unconnected-(U8-NC-Pad5)") (class "Default")
      (node (ref "U8") (pin "5") (pinfunction "NC_5") (pintype "passive+no_connect"))
    )
    (net (code "91") (name "unconnected-(U8-NC-Pad29)") (class "Default")
      (node (ref "U8") (pin "29") (pinfunction "NC_29") (pintype "passive+no_connect"))
    )
    (net (code "92") (name "unconnected-(U8-NC-Pad30)") (class "Default")
      (node (ref "U8") (pin "30") (pinfunction "NC_30") (pintype "passive+no_connect"))
    )
    (net (code "93") (name "unconnected-(U8-NC-Pad32)") (class "Default")
      (node (ref "U8") (pin "32") (pinfunction "NC_32") (pintype "passive+no_connect"))
    )
    (net (code "94") (name "unconnected-(U8-NC-Pad35)") (class "Default")
      (node (ref "U8") (pin "35") (pinfunction "NC_35") (pintype "passive+no_connect"))
    )
    (net (code "95") (name "unconnected-(U8-TP1(FM_AL)-Pad45)") (class "Default")
      (node (ref "U8") (pin "45") (pinfunction "TP1(FM_AL)_45") (pintype "passive+no_connect"))
    )
    (net (code "96") (name "unconnected-(U8-TP2(FM_AR)-Pad46)") (class "Default")
      (node (ref "U8") (pin "46") (pinfunction "TP2(FM_AR)_46") (pintype "passive+no_connect"))
    )
    (net (code "97") (name "unconnected-(U8-TP3(NC)-Pad47)") (class "Default")
      (node (ref "U8") (pin "47") (pinfunction "TP3(NC)_47") (pintype "passive+no_connect"))
    )
  )
)
